# STM32Fx.net
KiCad netlist of a schematic drawn in Altium Designer
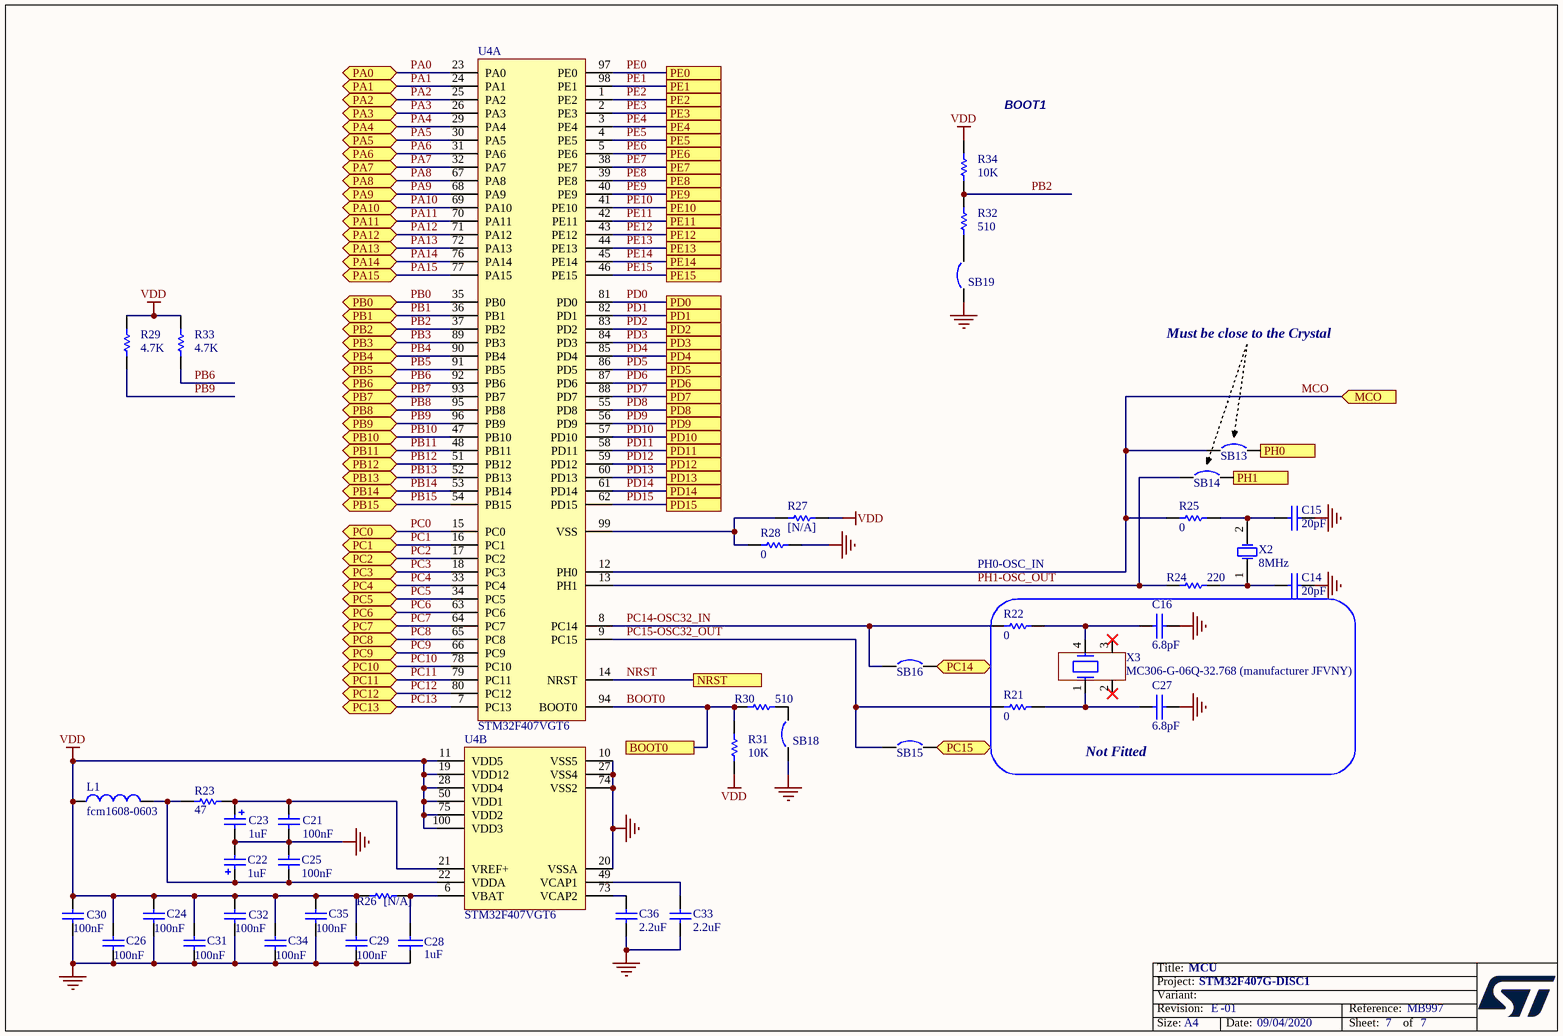
[diagram p0: STM32Fx.SchDoc]

(export (version "E")
  (design (tool "Eeschema 10.0.6"))
  (components
    (comp (ref "C14")
      (value "20pF")
      (footprint "0603C")
      (description "Capacitor")
      (libsource (lib "*") (part "CAP"))
    )
    (comp (ref "C15")
      (value "20pF")
      (footprint "0603C")
      (description "Capacitor")
      (libsource (lib "*") (part "CAP"))
    )
    (comp (ref "C16")
      (value "6.8pF")
      (footprint "0603C")
      (description "Capacitor")
      (libsource (lib "") (part "CAP_1"))
    )
    (comp (ref "C21")
      (value "100nF")
      (footprint "0402C")
      (description "Capacitor")
      (fields (field (name "PUBLISHER") "Altium Limited"))
      (libsource (lib "MB915_1") (part "Cap"))
    )
    (comp (ref "C22")
      (value "1uF")
      (footprint "CASE-A")
      (description "Polarized Capacitor (Radial)")
      (fields (field (name "PUBLISHER") "Altium Limited"))
      (libsource (lib "Miscellaneous Devices") (part "Cap Pol1"))
    )
    (comp (ref "C23")
      (value "1uF")
      (footprint "CASE-A")
      (description "Polarized Capacitor (Radial)")
      (fields (field (name "PUBLISHER") "Altium Limited"))
      (libsource (lib "Miscellaneous Devices") (part "Cap Pol1"))
    )
    (comp (ref "C24")
      (value "100nF")
      (footprint "0402C")
      (description "Capacitor")
      (fields (field (name "PUBLISHER") "Altium Limited"))
      (libsource (lib "MB915_1") (part "Cap"))
    )
    (comp (ref "C25")
      (value "100nF")
      (footprint "0402C")
      (description "Capacitor")
      (fields (field (name "PUBLISHER") "Altium Limited"))
      (libsource (lib "MB915_1") (part "Cap"))
    )
    (comp (ref "C26")
      (value "100nF")
      (footprint "0402C")
      (description "Capacitor")
      (fields (field (name "PUBLISHER") "Altium Limited"))
      (libsource (lib "MB915_1") (part "Cap"))
    )
    (comp (ref "C27")
      (value "6.8pF")
      (footprint "0603C")
      (description "Capacitor")
      (libsource (lib "") (part "CAP_1"))
    )
    (comp (ref "C28")
      (value "1uF")
      (footprint "0603C")
      (description "Capacitor")
      (libsource (lib "*") (part "CAP"))
    )
    (comp (ref "C29")
      (value "100nF")
      (footprint "0402C")
      (description "Capacitor")
      (fields (field (name "PUBLISHER") "Altium Limited"))
      (libsource (lib "MB915_1") (part "Cap"))
    )
    (comp (ref "C30")
      (value "100nF")
      (footprint "0402C")
      (description "Capacitor")
      (fields (field (name "PUBLISHER") "Altium Limited"))
      (libsource (lib "MB915_1") (part "Cap"))
    )
    (comp (ref "C31")
      (value "100nF")
      (footprint "0402C")
      (description "Capacitor")
      (fields (field (name "PUBLISHER") "Altium Limited"))
      (libsource (lib "MB915_1") (part "Cap"))
    )
    (comp (ref "C32")
      (value "100nF")
      (footprint "0402C")
      (description "Capacitor")
      (fields (field (name "PUBLISHER") "Altium Limited"))
      (libsource (lib "MB915_1") (part "Cap"))
    )
    (comp (ref "C33")
      (value "2.2uF")
      (footprint "CASE-A")
      (description "Low ESR Ceramic Capacitor (X7R)")
      (fields (field (name "PUBLISHER") "Altium Limited"))
      (libsource (lib "MB997") (part "Cap Low ESR"))
    )
    (comp (ref "C34")
      (value "100nF")
      (footprint "0402C")
      (description "Capacitor")
      (fields (field (name "PUBLISHER") "Altium Limited"))
      (libsource (lib "MB915_1") (part "Cap"))
    )
    (comp (ref "C35")
      (value "100nF")
      (footprint "0402C")
      (description "Capacitor")
      (fields (field (name "PUBLISHER") "Altium Limited"))
      (libsource (lib "MB915_1") (part "Cap"))
    )
    (comp (ref "C36")
      (value "2.2uF")
      (footprint "CASE-A")
      (description "Low ESR Ceramic Capacitor (X7R)")
      (fields (field (name "PUBLISHER") "Altium Limited"))
      (libsource (lib "MB997") (part "Cap Low ESR"))
    )
    (comp (ref "L1")
      (value "fcm1608-0603")
      (footprint "0603L")
      (description "Inductor")
      (fields (field (name "PUBLISHER") "Altium Limited"))
      (libsource (lib "Miscellaneous Devices") (part "Inductor"))
    )
    (comp (ref "R21")
      (value "0")
      (footprint "0603R")
      (description "Resistor")
      (fields (field (name "PUBLISHER") "Altium Limited"))
      (libsource (lib "Miscellaneous Devices") (part "Res1"))
    )
    (comp (ref "R22")
      (value "0")
      (footprint "0603R")
      (description "Resistor")
      (fields (field (name "PUBLISHER") "Altium Limited"))
      (libsource (lib "Miscellaneous Devices") (part "Res1"))
    )
    (comp (ref "R23")
      (value "47")
      (footprint "0603R")
      (description "Resistor")
      (fields (field (name "PUBLISHER") "Altium Limited"))
      (libsource (lib "Miscellaneous Devices") (part "Res1"))
    )
    (comp (ref "R24")
      (value "220")
      (footprint "0603R")
      (description "Resistor")
      (fields (field (name "PUBLISHER") "Altium Limited"))
      (libsource (lib "Miscellaneous Devices") (part "Res1"))
    )
    (comp (ref "R25")
      (value "0")
      (footprint "0603R")
      (description "Resistor")
      (fields (field (name "PUBLISHER") "Altium Limited"))
      (libsource (lib "Miscellaneous Devices") (part "Res1"))
    )
    (comp (ref "R26")
      (value "[N/A]")
      (footprint "0603R")
      (description "Resistor")
      (fields (field (name "PUBLISHER") "Altium Limited"))
      (libsource (lib "Miscellaneous Devices") (part "res1"))
    )
    (comp (ref "R27")
      (value "[N/A]")
      (footprint "0603R")
      (description "Resistor")
      (fields (field (name "PUBLISHER") "Altium Limited"))
      (libsource (lib "Miscellaneous Devices") (part "Res1"))
    )
    (comp (ref "R28")
      (value "0")
      (footprint "0603R")
      (description "Resistor")
      (fields (field (name "PUBLISHER") "Altium Limited"))
      (libsource (lib "Miscellaneous Devices") (part "Res1"))
    )
    (comp (ref "R29")
      (value "4.7K")
      (footprint "0402R")
      (description "Resistor")
      (fields (field (name "PUBLISHER") "Altium Limited"))
      (libsource (lib "Miscellaneous Devices") (part "res1"))
    )
    (comp (ref "R30")
      (value "510")
      (footprint "0603R")
      (description "Resistor")
      (fields (field (name "PUBLISHER") "Altium Limited"))
      (libsource (lib "Miscellaneous Devices") (part "Res1"))
    )
    (comp (ref "R31")
      (value "10K")
      (footprint "0402R")
      (description "Resistor")
      (fields (field (name "PUBLISHER") "Altium Limited"))
      (libsource (lib "Miscellaneous Devices") (part "res1"))
    )
    (comp (ref "R32")
      (value "510")
      (footprint "0603R")
      (description "Resistor")
      (fields (field (name "PUBLISHER") "Altium Limited"))
      (libsource (lib "Miscellaneous Devices") (part "res1"))
    )
    (comp (ref "R33")
      (value "4.7K")
      (footprint "0402R")
      (description "Resistor")
      (fields (field (name "PUBLISHER") "Altium Limited"))
      (libsource (lib "Miscellaneous Devices") (part "res1"))
    )
    (comp (ref "R34")
      (value "10K")
      (footprint "0402R")
      (description "Resistor")
      (fields (field (name "PUBLISHER") "Altium Limited"))
      (libsource (lib "Miscellaneous Devices") (part "res1"))
    )
    (comp (ref "SB13")
      (value "Circuit Breaker")
      (footprint "JUMPER")
      (fields (field (name "PUBLISHER") "Altium Limited"))
      (libsource (lib "MB915") (part "Circuit Breaker"))
    )
    (comp (ref "SB14")
      (value "Circuit Breaker")
      (footprint "JUMPER")
      (fields (field (name "PUBLISHER") "Altium Limited"))
      (libsource (lib "MB915") (part "Circuit Breaker"))
    )
    (comp (ref "SB15")
      (value "Circuit Breaker")
      (footprint "JUMPER")
      (fields (field (name "PUBLISHER") "Altium Limited"))
      (libsource (lib "MB915") (part "Circuit Breaker"))
    )
    (comp (ref "SB16")
      (value "Circuit Breaker")
      (footprint "JUMPER")
      (fields (field (name "PUBLISHER") "Altium Limited"))
      (libsource (lib "MB915") (part "Circuit Breaker"))
    )
    (comp (ref "SB18")
      (value "Circuit Breaker")
      (footprint "JUMPER")
      (fields (field (name "PUBLISHER") "Altium Limited"))
      (libsource (lib "MB915") (part "Circuit Breaker"))
    )
    (comp (ref "SB19")
      (value "Circuit Breaker")
      (footprint "JUMPER")
      (fields (field (name "PUBLISHER") "Altium Limited"))
      (libsource (lib "MB915") (part "Circuit Breaker"))
    )
    (comp (ref "U4")
      (value "STM32F407VGT6")
      (footprint "QFP100-1414")
      (description "STM32 Manta (STM32F407VGT6)")
      (libsource (lib "MCD_TOOLS") (part "STM32F407VGT6"))
    )
    (comp (ref "X2")
      (value "8MHz")
      (footprint "HC-49A")
      (description "Crystal Oscillator")
      (fields (field (name "PUBLISHER") "Altium Limited"))
      (libsource (lib "MB963_1") (part "XTAL"))
    )
    (comp (ref "X3")
      (value "MC306-G-06Q-32.768 (manufacturer JFVNY)")
      (footprint "MC306-CRYSTAL")
      (libsource (lib "*") (part "MC306"))
    )
  )
  (nets
    (net (code "1") (name "/BOOT0") (class "Default")
      (node (ref "R30") (pin "2") (pinfunction "2_2") (pintype "passive"))
      (node (ref "R31") (pin "1") (pinfunction "1_1") (pintype "passive"))
      (node (ref "U4") (pin "94") (pinfunction "BOOT0_94") (pintype "passive"))
    )
    (net (code "2") (name "/MCO") (class "Default")
      (node (ref "R25") (pin "1") (pinfunction "1_1") (pintype "passive"))
      (node (ref "SB13") (pin "1") (pinfunction "1_1") (pintype "passive"))
      (node (ref "U4") (pin "12") (pinfunction "PH0_12") (pintype "passive"))
    )
    (net (code "3") (name "/NRST") (class "Default")
      (node (ref "U4") (pin "14") (pinfunction "NRST_14") (pintype "passive"))
    )
    (net (code "4") (name "/PA0") (class "Default")
      (node (ref "U4") (pin "23") (pinfunction "PA0_23") (pintype "passive"))
    )
    (net (code "5") (name "/PA1") (class "Default")
      (node (ref "U4") (pin "24") (pinfunction "PA1_24") (pintype "passive"))
    )
    (net (code "6") (name "/PA2") (class "Default")
      (node (ref "U4") (pin "25") (pinfunction "PA2_25") (pintype "passive"))
    )
    (net (code "7") (name "/PA3") (class "Default")
      (node (ref "U4") (pin "26") (pinfunction "PA3_26") (pintype "passive"))
    )
    (net (code "8") (name "/PA4") (class "Default")
      (node (ref "U4") (pin "29") (pinfunction "PA4_29") (pintype "passive"))
    )
    (net (code "9") (name "/PA5") (class "Default")
      (node (ref "U4") (pin "30") (pinfunction "PA5_30") (pintype "passive"))
    )
    (net (code "10") (name "/PA6") (class "Default")
      (node (ref "U4") (pin "31") (pinfunction "PA6_31") (pintype "passive"))
    )
    (net (code "11") (name "/PA7") (class "Default")
      (node (ref "U4") (pin "32") (pinfunction "PA7_32") (pintype "passive"))
    )
    (net (code "12") (name "/PA8") (class "Default")
      (node (ref "U4") (pin "67") (pinfunction "PA8_67") (pintype "passive"))
    )
    (net (code "13") (name "/PA9") (class "Default")
      (node (ref "U4") (pin "68") (pinfunction "PA9_68") (pintype "passive"))
    )
    (net (code "14") (name "/PA10") (class "Default")
      (node (ref "U4") (pin "69") (pinfunction "PA10_69") (pintype "passive"))
    )
    (net (code "15") (name "/PA11") (class "Default")
      (node (ref "U4") (pin "70") (pinfunction "PA11_70") (pintype "passive"))
    )
    (net (code "16") (name "/PA12") (class "Default")
      (node (ref "U4") (pin "71") (pinfunction "PA12_71") (pintype "passive"))
    )
    (net (code "17") (name "/PA13") (class "Default")
      (node (ref "U4") (pin "72") (pinfunction "PA13_72") (pintype "passive"))
    )
    (net (code "18") (name "/PA14") (class "Default")
      (node (ref "U4") (pin "76") (pinfunction "PA14_76") (pintype "passive"))
    )
    (net (code "19") (name "/PA15") (class "Default")
      (node (ref "U4") (pin "77") (pinfunction "PA15_77") (pintype "passive"))
    )
    (net (code "20") (name "/PB0") (class "Default")
      (node (ref "U4") (pin "35") (pinfunction "PB0_35") (pintype "passive"))
    )
    (net (code "21") (name "/PB1") (class "Default")
      (node (ref "U4") (pin "36") (pinfunction "PB1_36") (pintype "passive"))
    )
    (net (code "22") (name "/PB2") (class "Default")
      (node (ref "R32") (pin "1") (pinfunction "1_1") (pintype "passive"))
      (node (ref "R34") (pin "2") (pinfunction "2_2") (pintype "passive"))
      (node (ref "U4") (pin "37") (pinfunction "PB2_37") (pintype "passive"))
    )
    (net (code "23") (name "/PB3") (class "Default")
      (node (ref "U4") (pin "89") (pinfunction "PB3_89") (pintype "passive"))
    )
    (net (code "24") (name "/PB4") (class "Default")
      (node (ref "U4") (pin "90") (pinfunction "PB4_90") (pintype "passive"))
    )
    (net (code "25") (name "/PB5") (class "Default")
      (node (ref "U4") (pin "91") (pinfunction "PB5_91") (pintype "passive"))
    )
    (net (code "26") (name "/PB6") (class "Default")
      (node (ref "R33") (pin "2") (pinfunction "2_2") (pintype "passive"))
      (node (ref "U4") (pin "92") (pinfunction "PB6_92") (pintype "passive"))
    )
    (net (code "27") (name "/PB7") (class "Default")
      (node (ref "U4") (pin "93") (pinfunction "PB7_93") (pintype "passive"))
    )
    (net (code "28") (name "/PB8") (class "Default")
      (node (ref "U4") (pin "95") (pinfunction "PB8_95") (pintype "passive"))
    )
    (net (code "29") (name "/PB9") (class "Default")
      (node (ref "R29") (pin "2") (pinfunction "2_2") (pintype "passive"))
      (node (ref "U4") (pin "96") (pinfunction "PB9_96") (pintype "passive"))
    )
    (net (code "30") (name "/PB10") (class "Default")
      (node (ref "U4") (pin "47") (pinfunction "PB10_47") (pintype "passive"))
    )
    (net (code "31") (name "/PB11") (class "Default")
      (node (ref "U4") (pin "48") (pinfunction "PB11_48") (pintype "passive"))
    )
    (net (code "32") (name "/PB12") (class "Default")
      (node (ref "U4") (pin "51") (pinfunction "PB12_51") (pintype "passive"))
    )
    (net (code "33") (name "/PB13") (class "Default")
      (node (ref "U4") (pin "52") (pinfunction "PB13_52") (pintype "passive"))
    )
    (net (code "34") (name "/PB14") (class "Default")
      (node (ref "U4") (pin "53") (pinfunction "PB14_53") (pintype "passive"))
    )
    (net (code "35") (name "/PB15") (class "Default")
      (node (ref "U4") (pin "54") (pinfunction "PB15_54") (pintype "passive"))
    )
    (net (code "36") (name "/PC0") (class "Default")
      (node (ref "U4") (pin "15") (pinfunction "PC0_15") (pintype "passive"))
    )
    (net (code "37") (name "/PC1") (class "Default")
      (node (ref "U4") (pin "16") (pinfunction "PC1_16") (pintype "passive"))
    )
    (net (code "38") (name "/PC2") (class "Default")
      (node (ref "U4") (pin "17") (pinfunction "PC2_17") (pintype "passive"))
    )
    (net (code "39") (name "/PC3") (class "Default")
      (node (ref "U4") (pin "18") (pinfunction "PC3_18") (pintype "passive"))
    )
    (net (code "40") (name "/PC4") (class "Default")
      (node (ref "U4") (pin "33") (pinfunction "PC4_33") (pintype "passive"))
    )
    (net (code "41") (name "/PC5") (class "Default")
      (node (ref "U4") (pin "34") (pinfunction "PC5_34") (pintype "passive"))
    )
    (net (code "42") (name "/PC6") (class "Default")
      (node (ref "U4") (pin "63") (pinfunction "PC6_63") (pintype "passive"))
    )
    (net (code "43") (name "/PC7") (class "Default")
      (node (ref "U4") (pin "64") (pinfunction "PC7_64") (pintype "passive"))
    )
    (net (code "44") (name "/PC8") (class "Default")
      (node (ref "U4") (pin "65") (pinfunction "PC8_65") (pintype "passive"))
    )
    (net (code "45") (name "/PC9") (class "Default")
      (node (ref "U4") (pin "66") (pinfunction "PC9_66") (pintype "passive"))
    )
    (net (code "46") (name "/PC10") (class "Default")
      (node (ref "U4") (pin "78") (pinfunction "PC10_78") (pintype "passive"))
    )
    (net (code "47") (name "/PC11") (class "Default")
      (node (ref "U4") (pin "79") (pinfunction "PC11_79") (pintype "passive"))
    )
    (net (code "48") (name "/PC12") (class "Default")
      (node (ref "U4") (pin "80") (pinfunction "PC12_80") (pintype "passive"))
    )
    (net (code "49") (name "/PC13") (class "Default")
      (node (ref "U4") (pin "7") (pinfunction "PC13_7") (pintype "passive"))
    )
    (net (code "50") (name "/PC14") (class "Default")
      (node (ref "SB16") (pin "2") (pinfunction "2_2") (pintype "passive"))
    )
    (net (code "51") (name "/PC14-OSC32_IN") (class "Default")
      (node (ref "R22") (pin "1") (pinfunction "1_1") (pintype "passive"))
      (node (ref "SB16") (pin "1") (pinfunction "1_1") (pintype "passive"))
      (node (ref "U4") (pin "8") (pinfunction "PC14_8") (pintype "passive"))
    )
    (net (code "52") (name "/PC15") (class "Default")
      (node (ref "SB15") (pin "2") (pinfunction "2_2") (pintype "passive"))
    )
    (net (code "53") (name "/PC15-OSC32_OUT") (class "Default")
      (node (ref "R21") (pin "1") (pinfunction "1_1") (pintype "passive"))
      (node (ref "SB15") (pin "1") (pinfunction "1_1") (pintype "passive"))
      (node (ref "U4") (pin "9") (pinfunction "PC15_9") (pintype "passive"))
    )
    (net (code "54") (name "/PD0") (class "Default")
      (node (ref "U4") (pin "81") (pinfunction "PD0_81") (pintype "passive"))
    )
    (net (code "55") (name "/PD1") (class "Default")
      (node (ref "U4") (pin "82") (pinfunction "PD1_82") (pintype "passive"))
    )
    (net (code "56") (name "/PD2") (class "Default")
      (node (ref "U4") (pin "83") (pinfunction "PD2_83") (pintype "passive"))
    )
    (net (code "57") (name "/PD3") (class "Default")
      (node (ref "U4") (pin "84") (pinfunction "PD3_84") (pintype "passive"))
    )
    (net (code "58") (name "/PD4") (class "Default")
      (node (ref "U4") (pin "85") (pinfunction "PD4_85") (pintype "passive"))
    )
    (net (code "59") (name "/PD5") (class "Default")
      (node (ref "U4") (pin "86") (pinfunction "PD5_86") (pintype "passive"))
    )
    (net (code "60") (name "/PD6") (class "Default")
      (node (ref "U4") (pin "87") (pinfunction "PD6_87") (pintype "passive"))
    )
    (net (code "61") (name "/PD7") (class "Default")
      (node (ref "U4") (pin "88") (pinfunction "PD7_88") (pintype "passive"))
    )
    (net (code "62") (name "/PD8") (class "Default")
      (node (ref "U4") (pin "55") (pinfunction "PD8_55") (pintype "passive"))
    )
    (net (code "63") (name "/PD9") (class "Default")
      (node (ref "U4") (pin "56") (pinfunction "PD9_56") (pintype "passive"))
    )
    (net (code "64") (name "/PD10") (class "Default")
      (node (ref "U4") (pin "57") (pinfunction "PD10_57") (pintype "passive"))
    )
    (net (code "65") (name "/PD11") (class "Default")
      (node (ref "U4") (pin "58") (pinfunction "PD11_58") (pintype "passive"))
    )
    (net (code "66") (name "/PD12") (class "Default")
      (node (ref "U4") (pin "59") (pinfunction "PD12_59") (pintype "passive"))
    )
    (net (code "67") (name "/PD13") (class "Default")
      (node (ref "U4") (pin "60") (pinfunction "PD13_60") (pintype "passive"))
    )
    (net (code "68") (name "/PD14") (class "Default")
      (node (ref "U4") (pin "61") (pinfunction "PD14_61") (pintype "passive"))
    )
    (net (code "69") (name "/PD15") (class "Default")
      (node (ref "U4") (pin "62") (pinfunction "PD15_62") (pintype "passive"))
    )
    (net (code "70") (name "/PE0") (class "Default")
      (node (ref "U4") (pin "97") (pinfunction "PE0_97") (pintype "passive"))
    )
    (net (code "71") (name "/PE1") (class "Default")
      (node (ref "U4") (pin "98") (pinfunction "PE1_98") (pintype "passive"))
    )
    (net (code "72") (name "/PE2") (class "Default")
      (node (ref "U4") (pin "1") (pinfunction "PE2_1") (pintype "passive"))
    )
    (net (code "73") (name "/PE3") (class "Default")
      (node (ref "U4") (pin "2") (pinfunction "PE3_2") (pintype "passive"))
    )
    (net (code "74") (name "/PE4") (class "Default")
      (node (ref "U4") (pin "3") (pinfunction "PE4_3") (pintype "passive"))
    )
    (net (code "75") (name "/PE5") (class "Default")
      (node (ref "U4") (pin "4") (pinfunction "PE5_4") (pintype "passive"))
    )
    (net (code "76") (name "/PE6") (class "Default")
      (node (ref "U4") (pin "5") (pinfunction "PE6_5") (pintype "passive"))
    )
    (net (code "77") (name "/PE7") (class "Default")
      (node (ref "U4") (pin "38") (pinfunction "PE7_38") (pintype "passive"))
    )
    (net (code "78") (name "/PE8") (class "Default")
      (node (ref "U4") (pin "39") (pinfunction "PE8_39") (pintype "passive"))
    )
    (net (code "79") (name "/PE9") (class "Default")
      (node (ref "U4") (pin "40") (pinfunction "PE9_40") (pintype "passive"))
    )
    (net (code "80") (name "/PE10") (class "Default")
      (node (ref "U4") (pin "41") (pinfunction "PE10_41") (pintype "passive"))
    )
    (net (code "81") (name "/PE11") (class "Default")
      (node (ref "U4") (pin "42") (pinfunction "PE11_42") (pintype "passive"))
    )
    (net (code "82") (name "/PE12") (class "Default")
      (node (ref "U4") (pin "43") (pinfunction "PE12_43") (pintype "passive"))
    )
    (net (code "83") (name "/PE13") (class "Default")
      (node (ref "U4") (pin "44") (pinfunction "PE13_44") (pintype "passive"))
    )
    (net (code "84") (name "/PE14") (class "Default")
      (node (ref "U4") (pin "45") (pinfunction "PE14_45") (pintype "passive"))
    )
    (net (code "85") (name "/PE15") (class "Default")
      (node (ref "U4") (pin "46") (pinfunction "PE15_46") (pintype "passive"))
    )
    (net (code "86") (name "/PH0") (class "Default")
      (node (ref "SB13") (pin "2") (pinfunction "2_2") (pintype "passive"))
    )
    (net (code "87") (name "/PH1") (class "Default")
      (node (ref "SB14") (pin "2") (pinfunction "2_2") (pintype "passive"))
    )
    (net (code "88") (name "/PH1-OSC_OUT") (class "Default")
      (node (ref "R24") (pin "2") (pinfunction "2_2") (pintype "passive"))
      (node (ref "SB14") (pin "1") (pinfunction "1_1") (pintype "passive"))
      (node (ref "U4") (pin "13") (pinfunction "PH1_13") (pintype "passive"))
    )
    (net (code "89") (name "GND") (class "Default")
      (node (ref "C14") (pin "1") (pinfunction "1_1") (pintype "passive"))
      (node (ref "C15") (pin "1") (pinfunction "1_1") (pintype "passive"))
      (node (ref "C16") (pin "2") (pinfunction "2_2") (pintype "passive"))
      (node (ref "C21") (pin "1") (pinfunction "1_1") (pintype "passive"))
      (node (ref "C22") (pin "2") (pinfunction "2_2") (pintype "passive"))
      (node (ref "C23") (pin "2") (pinfunction "2_2") (pintype "passive"))
      (node (ref "C24") (pin "2") (pinfunction "2_2") (pintype "passive"))
      (node (ref "C25") (pin "1") (pinfunction "1_1") (pintype "passive"))
      (node (ref "C26") (pin "1") (pinfunction "1_1") (pintype "passive"))
      (node (ref "C27") (pin "2") (pinfunction "2_2") (pintype "passive"))
      (node (ref "C28") (pin "2") (pinfunction "2_2") (pintype "passive"))
      (node (ref "C29") (pin "1") (pinfunction "1_1") (pintype "passive"))
      (node (ref "C30") (pin "1") (pinfunction "1_1") (pintype "passive"))
      (node (ref "C31") (pin "1") (pinfunction "1_1") (pintype "passive"))
      (node (ref "C32") (pin "1") (pinfunction "1_1") (pintype "passive"))
      (node (ref "C33") (pin "2") (pinfunction "2_2") (pintype "passive"))
      (node (ref "C34") (pin "1") (pinfunction "1_1") (pintype "passive"))
      (node (ref "C35") (pin "2") (pinfunction "2_2") (pintype "passive"))
      (node (ref "C36") (pin "2") (pinfunction "2_2") (pintype "passive"))
      (node (ref "R28") (pin "2") (pinfunction "2_2") (pintype "passive"))
      (node (ref "SB18") (pin "1") (pinfunction "1_1") (pintype "passive"))
      (node (ref "SB19") (pin "1") (pinfunction "1_1") (pintype "passive"))
      (node (ref "U4") (pin "10") (pinfunction "VSS5_10") (pintype "passive"))
      (node (ref "U4") (pin "20") (pinfunction "VSSA_20") (pintype "passive"))
      (node (ref "U4") (pin "27") (pinfunction "VSS4_27") (pintype "passive"))
      (node (ref "U4") (pin "74") (pinfunction "VSS2_74") (pintype "passive"))
    )
    (net (code "90") (name "Net-(C16-Pad1)") (class "Default")
      (node (ref "C16") (pin "1") (pinfunction "1_1") (pintype "passive"))
      (node (ref "R22") (pin "2") (pinfunction "2_2") (pintype "passive"))
      (node (ref "X3") (pin "4") (pinfunction "4_4") (pintype "passive"))
    )
    (net (code "91") (name "Net-(C27-Pad1)") (class "Default")
      (node (ref "C27") (pin "1") (pinfunction "1_1") (pintype "passive"))
      (node (ref "R21") (pin "2") (pinfunction "2_2") (pintype "passive"))
      (node (ref "X3") (pin "1") (pinfunction "1_1") (pintype "passive"))
    )
    (net (code "92") (name "Net-(R30-Pad1)") (class "Default")
      (node (ref "R30") (pin "1") (pinfunction "1_1") (pintype "passive"))
      (node (ref "SB18") (pin "2") (pinfunction "2_2") (pintype "passive"))
    )
    (net (code "93") (name "Net-(R32-Pad2)") (class "Default")
      (node (ref "R32") (pin "2") (pinfunction "2_2") (pintype "passive"))
      (node (ref "SB19") (pin "2") (pinfunction "2_2") (pintype "passive"))
    )
    (net (code "94") (name "Net-(U4A-VSS)") (class "Default")
      (node (ref "R27") (pin "1") (pinfunction "1_1") (pintype "passive"))
      (node (ref "R28") (pin "1") (pinfunction "1_1") (pintype "passive"))
      (node (ref "U4") (pin "99") (pinfunction "VSS_99") (pintype "passive"))
    )
    (net (code "95") (name "Net-(U4B-VBAT)") (class "Default")
      (node (ref "C28") (pin "1") (pinfunction "1_1") (pintype "passive"))
      (node (ref "R26") (pin "2") (pinfunction "2_2") (pintype "passive"))
      (node (ref "U4") (pin "6") (pinfunction "VBAT_6") (pintype "passive"))
    )
    (net (code "96") (name "Net-(U4B-VCAP1)") (class "Default")
      (node (ref "C33") (pin "1") (pinfunction "1_1") (pintype "passive"))
      (node (ref "U4") (pin "49") (pinfunction "VCAP1_49") (pintype "passive"))
    )
    (net (code "97") (name "Net-(U4B-VCAP2)") (class "Default")
      (node (ref "C36") (pin "1") (pinfunction "1_1") (pintype "passive"))
      (node (ref "U4") (pin "73") (pinfunction "VCAP2_73") (pintype "passive"))
    )
    (net (code "98") (name "Net-(U4B-VDDA)") (class "Default")
      (node (ref "C22") (pin "1") (pinfunction "1_1") (pintype "passive"))
      (node (ref "C25") (pin "2") (pinfunction "2_2") (pintype "passive"))
      (node (ref "L1") (pin "2") (pinfunction "2_2") (pintype "passive"))
      (node (ref "R23") (pin "2") (pinfunction "2_2") (pintype "passive"))
      (node (ref "U4") (pin "22") (pinfunction "VDDA_22") (pintype "passive"))
    )
    (net (code "99") (name "Net-(U4B-VREF+)") (class "Default")
      (node (ref "C21") (pin "2") (pinfunction "2_2") (pintype "passive"))
      (node (ref "C23") (pin "1") (pinfunction "1_1") (pintype "passive"))
      (node (ref "R23") (pin "1") (pinfunction "1_1") (pintype "passive"))
      (node (ref "U4") (pin "21") (pinfunction "VREF+_21") (pintype "passive"))
    )
    (net (code "100") (name "Net-(X2-OSC1)") (class "Default")
      (node (ref "C14") (pin "2") (pinfunction "2_2") (pintype "passive"))
      (node (ref "R24") (pin "1") (pinfunction "1_1") (pintype "passive"))
      (node (ref "X2") (pin "1") (pinfunction "OSC1_1") (pintype "passive"))
    )
    (net (code "101") (name "Net-(X2-OSC2)") (class "Default")
      (node (ref "C15") (pin "2") (pinfunction "2_2") (pintype "passive"))
      (node (ref "R25") (pin "2") (pinfunction "2_2") (pintype "passive"))
      (node (ref "X2") (pin "2") (pinfunction "OSC2_2") (pintype "passive"))
    )
    (net (code "102") (name "VDD") (class "Default")
      (node (ref "C24") (pin "1") (pinfunction "1_1") (pintype "passive"))
      (node (ref "C26") (pin "2") (pinfunction "2_2") (pintype "passive"))
      (node (ref "C29") (pin "2") (pinfunction "2_2") (pintype "passive"))
      (node (ref "C30") (pin "2") (pinfunction "2_2") (pintype "passive"))
      (node (ref "C31") (pin "2") (pinfunction "2_2") (pintype "passive"))
      (node (ref "C32") (pin "2") (pinfunction "2_2") (pintype "passive"))
      (node (ref "C34") (pin "2") (pinfunction "2_2") (pintype "passive"))
      (node (ref "C35") (pin "1") (pinfunction "1_1") (pintype "passive"))
      (node (ref "L1") (pin "1") (pinfunction "1_1") (pintype "passive"))
      (node (ref "R26") (pin "1") (pinfunction "1_1") (pintype "passive"))
      (node (ref "R27") (pin "2") (pinfunction "2_2") (pintype "passive"))
      (node (ref "R29") (pin "1") (pinfunction "1_1") (pintype "passive"))
      (node (ref "R31") (pin "2") (pinfunction "2_2") (pintype "passive"))
      (node (ref "R33") (pin "1") (pinfunction "1_1") (pintype "passive"))
      (node (ref "R34") (pin "1") (pinfunction "1_1") (pintype "passive"))
      (node (ref "U4") (pin "100") (pinfunction "VDD3_100") (pintype "passive"))
      (node (ref "U4") (pin "11") (pinfunction "VDD5_11") (pintype "passive"))
      (node (ref "U4") (pin "19") (pinfunction "VDD12_19") (pintype "passive"))
      (node (ref "U4") (pin "28") (pinfunction "VDD4_28") (pintype "passive"))
      (node (ref "U4") (pin "50") (pinfunction "VDD1_50") (pintype "passive"))
      (node (ref "U4") (pin "75") (pinfunction "VDD2_75") (pintype "passive"))
    )
    (net (code "103") (name "unconnected-(X3-Pad2)") (class "Default")
      (node (ref "X3") (pin "2") (pinfunction "2_2") (pintype "passive+no_connect"))
    )
    (net (code "104") (name "unconnected-(X3-Pad3)") (class "Default")
      (node (ref "X3") (pin "3") (pinfunction "3_3") (pintype "passive+no_connect"))
    )
  )
)
